# Sheet1.net
KiCad netlist of a schematic drawn in Altium Designer
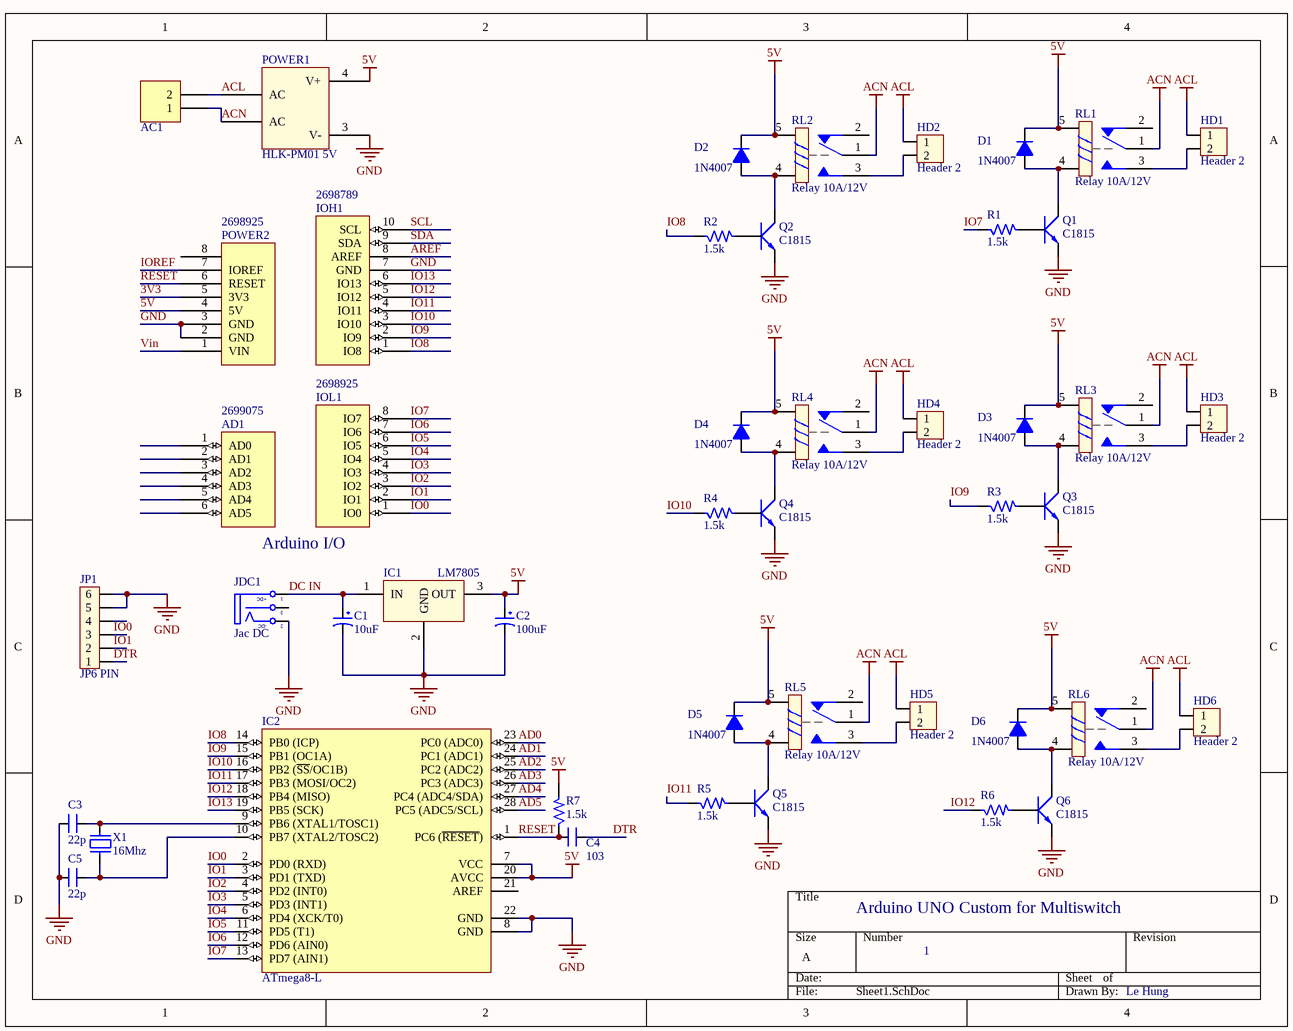
[diagram p0: Sheet1.SchDoc]

(export (version "E")
  (design (tool "Eeschema 10.0.6"))
  (components
    (comp (ref "AC1")
      (value "Header 2_1")
      (footprint "HED2")
      (description "Header, 2-Pin")
      (fields (field (name "MANUFACTURER") "Generic Components"))
      (libsource (lib "syhaunguyen") (part "Header 2_1"))
    )
    (comp (ref "AD1")
      (value "AD")
      (footprint "Header:Header 6x1 8.5mm")
      (fields (field (name "SUPPLIER PART NUMBER 4") "2699075"))
      (libsource (lib "Header") (part "AD"))
    )
    (comp (ref "C1")
      (value "10uF")
      (footprint "CP1/2")
      (description "Cap P  0,1uF < 22uF , 16 - 50V")
      (libsource (lib "syhaunguyen") (part "CP1"))
    )
    (comp (ref "C2")
      (value "100uF")
      (footprint "CP1/2")
      (description "Cap P  0,1uF < 22uF , 16 - 50V")
      (libsource (lib "syhaunguyen") (part "CP1"))
    )
    (comp (ref "C3")
      (value "22p")
      (footprint "CN1.5")
      (description "Cap np 682pF => 104pF")
      (libsource (lib "syhaunguyen") (part "CN1.5"))
    )
    (comp (ref "C4")
      (value "103")
      (footprint "CN1.5")
      (description "Cap np 682pF => 104pF")
      (libsource (lib "syhaunguyen") (part "CN1.5"))
    )
    (comp (ref "C5")
      (value "22p")
      (footprint "CN1.5")
      (description "Cap np 682pF => 104pF")
      (libsource (lib "syhaunguyen") (part "CN1.5"))
    )
    (comp (ref "D1")
      (value "1N4007")
      (footprint "D1A")
      (description "Diode 1A")
      (libsource (lib "syhaunguyen") (part "D1A"))
    )
    (comp (ref "D2")
      (value "1N4007")
      (footprint "D1A")
      (description "Diode 1A")
      (libsource (lib "syhaunguyen") (part "D1A"))
    )
    (comp (ref "D3")
      (value "1N4007")
      (footprint "D1A")
      (description "Diode 1A")
      (libsource (lib "syhaunguyen") (part "D1A"))
    )
    (comp (ref "D4")
      (value "1N4007")
      (footprint "D1A")
      (description "Diode 1A")
      (libsource (lib "syhaunguyen") (part "D1A"))
    )
    (comp (ref "D5")
      (value "1N4007")
      (footprint "D1A")
      (description "Diode 1A")
      (libsource (lib "syhaunguyen") (part "D1A"))
    )
    (comp (ref "D6")
      (value "1N4007")
      (footprint "D1A")
      (description "Diode 1A")
      (libsource (lib "syhaunguyen") (part "D1A"))
    )
    (comp (ref "HD1")
      (value "Header 2")
      (footprint "HED2")
      (description "Header 2 (Green)")
      (libsource (lib "VioletofSun") (part "Hed2"))
    )
    (comp (ref "HD2")
      (value "Header 2")
      (footprint "HED2")
      (description "Header 2 (Green)")
      (libsource (lib "VioletofSun") (part "Hed2"))
    )
    (comp (ref "HD3")
      (value "Header 2")
      (footprint "HED2")
      (description "Header 2 (Green)")
      (libsource (lib "VioletofSun") (part "Hed2"))
    )
    (comp (ref "HD4")
      (value "Header 2")
      (footprint "HED2")
      (description "Header 2 (Green)")
      (libsource (lib "VioletofSun") (part "Hed2"))
    )
    (comp (ref "HD5")
      (value "Header 2")
      (footprint "HED2")
      (description "Header 2 (Green)")
      (libsource (lib "VioletofSun") (part "Hed2"))
    )
    (comp (ref "HD6")
      (value "Header 2")
      (footprint "HED2")
      (description "Header 2 (Green)")
      (libsource (lib "VioletofSun") (part "Hed2"))
    )
    (comp (ref "IC1")
      (value "LM7805")
      (footprint "QTO-220")
      (description "On ap +, from + 5 to + 24VDC")
      (libsource (lib "syhaunguyen") (part "LM78xx"))
    )
    (comp (ref "IC2")
      (value "ATmega8-L")
      (footprint "DIP28/W0.3")
      (description "8-Bit AVR Microcontroller with 8K Bytes of In-System Programmable Flash Memory")
      (libsource (lib "syhaunguyen") (part "ATmega8-L"))
    )
    (comp (ref "IOH1")
      (value "IOH")
      (footprint "Header:Header 10x1 8.5mm")
      (fields (field (name "SUPPLIER PART NUMBER 3") "2698789"))
      (libsource (lib "Header") (part "IOH"))
    )
    (comp (ref "IOL1")
      (value "IOL")
      (footprint "Header 8x1 8.5mm")
      (fields (field (name "SUPPLIER PART NUMBER 4") "2698925"))
      (libsource (lib "Header") (part "IOL"))
    )
    (comp (ref "JDC1")
      (value "Jac DC")
      (footprint "DC-IN")
      (description "Jac DC input")
      (libsource (lib "syhaunguyen") (part "DCIN"))
    )
    (comp (ref "JP1") (value "JP6 PIN") (footprint "JP6") (libsource (lib "syhaunguyen") (part "JP6")))
    (comp (ref "POWER1")
      (value "HLK-PM01 5V")
      (footprint "HK LINK")
      (description "Hi-link HLK-PM01")
      (libsource (lib "Schlib1") (part "Hi link"))
    )
    (comp (ref "POWER2")
      (value "POWER_UNO")
      (footprint "Header 8x1 8.5mm")
      (fields (field (name "SUPPLIER PART NUMBER 4") "2698925"))
      (libsource (lib "Header") (part "POWER_UNO"))
    )
    (comp (ref "Q1")
      (value "C1815")
      (footprint "QTO-92")
      (description "NPN 600mW, ECB")
      (libsource (lib "syhaunguyen") (part "C1815"))
    )
    (comp (ref "Q2")
      (value "C1815")
      (footprint "QTO-92")
      (description "NPN 600mW, ECB")
      (libsource (lib "syhaunguyen") (part "C1815"))
    )
    (comp (ref "Q3")
      (value "C1815")
      (footprint "QTO-92")
      (description "NPN 600mW, ECB")
      (libsource (lib "syhaunguyen") (part "C1815"))
    )
    (comp (ref "Q4")
      (value "C1815")
      (footprint "QTO-92")
      (description "NPN 600mW, ECB")
      (libsource (lib "syhaunguyen") (part "C1815"))
    )
    (comp (ref "Q5")
      (value "C1815")
      (footprint "QTO-92")
      (description "NPN 600mW, ECB")
      (libsource (lib "syhaunguyen") (part "C1815"))
    )
    (comp (ref "Q6")
      (value "C1815")
      (footprint "QTO-92")
      (description "NPN 600mW, ECB")
      (libsource (lib "syhaunguyen") (part "C1815"))
    )
    (comp (ref "R1")
      (value "1.5k")
      (footprint "R1/4W")
      (description "Resistor 1/4W")
      (libsource (lib "syhaunguyen") (part "R"))
    )
    (comp (ref "R2")
      (value "1.5k")
      (footprint "R1/4W")
      (description "Resistor 1/4W")
      (libsource (lib "syhaunguyen") (part "R"))
    )
    (comp (ref "R3")
      (value "1.5k")
      (footprint "R1/4W")
      (description "Resistor 1/4W")
      (libsource (lib "syhaunguyen") (part "R"))
    )
    (comp (ref "R4")
      (value "1.5k")
      (footprint "R1/4W")
      (description "Resistor 1/4W")
      (libsource (lib "syhaunguyen") (part "R"))
    )
    (comp (ref "R5")
      (value "1.5k")
      (footprint "R1/4W")
      (description "Resistor 1/4W")
      (libsource (lib "syhaunguyen") (part "R"))
    )
    (comp (ref "R6")
      (value "1.5k")
      (footprint "R1/4W")
      (description "Resistor 1/4W")
      (libsource (lib "syhaunguyen") (part "R"))
    )
    (comp (ref "R7")
      (value "1.5k")
      (footprint "R1/4W")
      (description "Resistor 1/4W")
      (libsource (lib "syhaunguyen") (part "R"))
    )
    (comp (ref "RL1")
      (value "Relay 10A/12V")
      (footprint "RL_SPDT_10A")
      (description "Relay SPDT,10A - 12VDC 5 Pin")
      (libsource (lib "syhaunguyen") (part "Relay 1"))
    )
    (comp (ref "RL2")
      (value "Relay 10A/12V")
      (footprint "RL_SPDT_10A")
      (description "Relay SPDT,10A - 12VDC 5 Pin")
      (libsource (lib "syhaunguyen") (part "Relay 1"))
    )
    (comp (ref "RL3")
      (value "Relay 10A/12V")
      (footprint "RL_SPDT_10A")
      (description "Relay SPDT,10A - 12VDC 5 Pin")
      (libsource (lib "syhaunguyen") (part "Relay 1"))
    )
    (comp (ref "RL4")
      (value "Relay 10A/12V")
      (footprint "RL_SPDT_10A")
      (description "Relay SPDT,10A - 12VDC 5 Pin")
      (libsource (lib "syhaunguyen") (part "Relay 1"))
    )
    (comp (ref "RL5")
      (value "Relay 10A/12V")
      (footprint "RL_SPDT_10A")
      (description "Relay SPDT,10A - 12VDC 5 Pin")
      (libsource (lib "syhaunguyen") (part "Relay 1"))
    )
    (comp (ref "RL6")
      (value "Relay 10A/12V")
      (footprint "RL_SPDT_10A")
      (description "Relay SPDT,10A - 12VDC 5 Pin")
      (libsource (lib "syhaunguyen") (part "Relay 1"))
    )
    (comp (ref "X1")
      (value "16Mhz")
      (footprint "XT2")
      (description "Crystal For all Crystal 2pin.")
      (libsource (lib "syhaunguyen") (part "XT2"))
    )
  )
  (nets
    (net (code "1") (name "/3V3") (class "Default")
      (node (ref "POWER2") (pin "5") (pinfunction "3V3_5") (pintype "power_in"))
    )
    (net (code "3") (name "/AD0") (class "Default")
      (node (ref "IC2") (pin "23") (pinfunction "PC0_(ADC0)_23") (pintype "bidirectional"))
    )
    (net (code "4") (name "/AD1") (class "Default")
      (node (ref "IC2") (pin "24") (pinfunction "PC1_(ADC1)_24") (pintype "bidirectional"))
    )
    (net (code "5") (name "/AD2") (class "Default")
      (node (ref "IC2") (pin "25") (pinfunction "PC2_(ADC2)_25") (pintype "bidirectional"))
    )
    (net (code "6") (name "/AD3") (class "Default")
      (node (ref "IC2") (pin "26") (pinfunction "PC3_(ADC3)_26") (pintype "bidirectional"))
    )
    (net (code "7") (name "/AD4") (class "Default")
      (node (ref "IC2") (pin "27") (pinfunction "PC4_(ADC4/SDA)_27") (pintype "bidirectional"))
    )
    (net (code "8") (name "/AD5") (class "Default")
      (node (ref "IC2") (pin "28") (pinfunction "PC5_(ADC5/SCL)_28") (pintype "bidirectional"))
    )
    (net (code "9") (name "/AREF") (class "Default")
      (node (ref "IOH1") (pin "8") (pinfunction "AREF_8") (pintype "passive"))
    )
    (net (code "10") (name "/DC IN") (class "Default")
      (node (ref "C1") (pin "1") (pinfunction "1_1") (pintype "passive"))
      (node (ref "IC1") (pin "1") (pinfunction "IN_1") (pintype "passive"))
      (node (ref "JDC1") (pin "1") (pinfunction "T_1") (pintype "passive"))
    )
    (net (code "11") (name "/DTR") (class "Default")
      (node (ref "C4") (pin "2") (pinfunction "2_2") (pintype "passive"))
      (node (ref "JP1") (pin "1") (pinfunction "1_1") (pintype "passive"))
    )
    (net (code "12") (name "/IO0") (class "Default")
      (node (ref "IC2") (pin "2") (pinfunction "PD0_(RXD)_2") (pintype "bidirectional"))
      (node (ref "IOL1") (pin "1") (pinfunction "IO0_1") (pintype "bidirectional"))
      (node (ref "JP1") (pin "3") (pinfunction "3_3") (pintype "passive"))
    )
    (net (code "13") (name "/IO1") (class "Default")
      (node (ref "IC2") (pin "3") (pinfunction "PD1_(TXD)_3") (pintype "bidirectional"))
      (node (ref "IOL1") (pin "2") (pinfunction "IO1_2") (pintype "bidirectional"))
      (node (ref "JP1") (pin "2") (pinfunction "2_2") (pintype "passive"))
    )
    (net (code "14") (name "/IO2") (class "Default")
      (node (ref "IC2") (pin "4") (pinfunction "PD2_(INT0)_4") (pintype "bidirectional"))
      (node (ref "IOL1") (pin "3") (pinfunction "IO2_3") (pintype "bidirectional"))
    )
    (net (code "15") (name "/IO3") (class "Default")
      (node (ref "IC2") (pin "5") (pinfunction "PD3_(INT1)_5") (pintype "bidirectional"))
      (node (ref "IOL1") (pin "4") (pinfunction "IO3_4") (pintype "bidirectional"))
    )
    (net (code "16") (name "/IO4") (class "Default")
      (node (ref "IC2") (pin "6") (pinfunction "PD4_(XCK/T0)_6") (pintype "bidirectional"))
      (node (ref "IOL1") (pin "5") (pinfunction "IO4_5") (pintype "bidirectional"))
    )
    (net (code "17") (name "/IO5") (class "Default")
      (node (ref "IC2") (pin "11") (pinfunction "PD5_(T1)_11") (pintype "bidirectional"))
      (node (ref "IOL1") (pin "6") (pinfunction "IO5_6") (pintype "bidirectional"))
    )
    (net (code "18") (name "/IO6") (class "Default")
      (node (ref "IC2") (pin "12") (pinfunction "PD6_(AIN0)_12") (pintype "bidirectional"))
      (node (ref "IOL1") (pin "7") (pinfunction "IO6_7") (pintype "bidirectional"))
    )
    (net (code "19") (name "/IO7") (class "Default")
      (node (ref "IC2") (pin "13") (pinfunction "PD7_(AIN1)_13") (pintype "bidirectional"))
      (node (ref "IOL1") (pin "8") (pinfunction "IO7_8") (pintype "bidirectional"))
      (node (ref "R1") (pin "1") (pinfunction "1_1") (pintype "passive"))
    )
    (net (code "20") (name "/IO8") (class "Default")
      (node (ref "IC2") (pin "14") (pinfunction "PB0_(ICP)_14") (pintype "bidirectional"))
      (node (ref "IOH1") (pin "1") (pinfunction "IO8_1") (pintype "bidirectional"))
      (node (ref "R2") (pin "1") (pinfunction "1_1") (pintype "passive"))
    )
    (net (code "21") (name "/IO9") (class "Default")
      (node (ref "IC2") (pin "15") (pinfunction "PB1_(OC1A)_15") (pintype "bidirectional"))
      (node (ref "IOH1") (pin "2") (pinfunction "IO9_2") (pintype "bidirectional"))
      (node (ref "R3") (pin "1") (pinfunction "1_1") (pintype "passive"))
    )
    (net (code "22") (name "/IO10") (class "Default")
      (node (ref "IC2") (pin "16") (pinfunction "PB2_(~{SS}/OC1B)_16") (pintype "bidirectional"))
      (node (ref "IOH1") (pin "3") (pinfunction "IO10_3") (pintype "bidirectional"))
      (node (ref "R4") (pin "1") (pinfunction "1_1") (pintype "passive"))
    )
    (net (code "23") (name "/IO11") (class "Default")
      (node (ref "IC2") (pin "17") (pinfunction "PB3_(MOSI/OC2)_17") (pintype "bidirectional"))
      (node (ref "IOH1") (pin "4") (pinfunction "IO11_4") (pintype "bidirectional"))
      (node (ref "R5") (pin "1") (pinfunction "1_1") (pintype "passive"))
    )
    (net (code "24") (name "/IO12") (class "Default")
      (node (ref "IC2") (pin "18") (pinfunction "PB4_(MISO)_18") (pintype "bidirectional"))
      (node (ref "IOH1") (pin "5") (pinfunction "IO12_5") (pintype "bidirectional"))
      (node (ref "R6") (pin "1") (pinfunction "1_1") (pintype "passive"))
    )
    (net (code "25") (name "/IO13") (class "Default")
      (node (ref "IC2") (pin "19") (pinfunction "PB5_(SCK)_19") (pintype "bidirectional"))
      (node (ref "IOH1") (pin "6") (pinfunction "IO13_6") (pintype "bidirectional"))
    )
    (net (code "26") (name "/IOREF") (class "Default")
      (node (ref "POWER2") (pin "7") (pinfunction "IOREF_7") (pintype "power_in"))
    )
    (net (code "27") (name "/RESET") (class "Default")
      (node (ref "C4") (pin "1") (pinfunction "1_1") (pintype "passive"))
      (node (ref "IC2") (pin "1") (pinfunction "PC6_(~{RESET})_1") (pintype "bidirectional"))
      (node (ref "POWER2") (pin "6") (pinfunction "RESET_6") (pintype "passive"))
      (node (ref "R7") (pin "1") (pinfunction "1_1") (pintype "passive"))
    )
    (net (code "28") (name "/SCL") (class "Default")
      (node (ref "IOH1") (pin "10") (pinfunction "SCL_10") (pintype "bidirectional"))
    )
    (net (code "29") (name "/SDA") (class "Default")
      (node (ref "IOH1") (pin "9") (pinfunction "SDA_9") (pintype "bidirectional"))
    )
    (net (code "30") (name "/Vin") (class "Default")
      (node (ref "POWER2") (pin "1") (pinfunction "VIN_1") (pintype "power_in"))
    )
    (net (code "31") (name "5V") (class "Default")
      (node (ref "C2") (pin "1") (pinfunction "1_1") (pintype "passive"))
      (node (ref "D1") (pin "2") (pinfunction "K_2") (pintype "passive"))
      (node (ref "D2") (pin "2") (pinfunction "K_2") (pintype "passive"))
      (node (ref "D3") (pin "2") (pinfunction "K_2") (pintype "passive"))
      (node (ref "D4") (pin "2") (pinfunction "K_2") (pintype "passive"))
      (node (ref "D5") (pin "2") (pinfunction "K_2") (pintype "passive"))
      (node (ref "D6") (pin "2") (pinfunction "K_2") (pintype "passive"))
      (node (ref "IC1") (pin "3") (pinfunction "OUT_3") (pintype "passive"))
      (node (ref "IC2") (pin "20") (pinfunction "AVCC_20") (pintype "power_in"))
      (node (ref "IC2") (pin "7") (pinfunction "VCC_7") (pintype "power_in"))
      (node (ref "POWER1") (pin "4") (pinfunction "V+_4") (pintype "passive"))
      (node (ref "POWER2") (pin "4") (pinfunction "5V_4") (pintype "power_in"))
      (node (ref "R7") (pin "2") (pinfunction "2_2") (pintype "passive"))
      (node (ref "RL1") (pin "5") (pinfunction "5_5") (pintype "passive"))
      (node (ref "RL2") (pin "5") (pinfunction "5_5") (pintype "passive"))
      (node (ref "RL3") (pin "5") (pinfunction "5_5") (pintype "passive"))
      (node (ref "RL4") (pin "5") (pinfunction "5_5") (pintype "passive"))
      (node (ref "RL5") (pin "5") (pinfunction "5_5") (pintype "passive"))
      (node (ref "RL6") (pin "5") (pinfunction "5_5") (pintype "passive"))
    )
    (net (code "32") (name "ACL") (class "Default")
      (node (ref "AC1") (pin "2") (pinfunction "2_2") (pintype "passive"))
      (node (ref "HD1") (pin "1") (pinfunction "1_1") (pintype "passive"))
      (node (ref "HD2") (pin "1") (pinfunction "1_1") (pintype "passive"))
      (node (ref "HD3") (pin "1") (pinfunction "1_1") (pintype "passive"))
      (node (ref "HD4") (pin "1") (pinfunction "1_1") (pintype "passive"))
      (node (ref "HD5") (pin "1") (pinfunction "1_1") (pintype "passive"))
      (node (ref "HD6") (pin "1") (pinfunction "1_1") (pintype "passive"))
      (node (ref "POWER1") (pin "2") (pinfunction "AC_2") (pintype "passive"))
    )
    (net (code "33") (name "ACN") (class "Default")
      (node (ref "AC1") (pin "1") (pinfunction "1_1") (pintype "passive"))
      (node (ref "POWER1") (pin "1") (pinfunction "AC_1") (pintype "passive"))
      (node (ref "RL1") (pin "1") (pinfunction "1_1") (pintype "passive"))
      (node (ref "RL2") (pin "1") (pinfunction "1_1") (pintype "passive"))
      (node (ref "RL3") (pin "1") (pinfunction "1_1") (pintype "passive"))
      (node (ref "RL4") (pin "1") (pinfunction "1_1") (pintype "passive"))
      (node (ref "RL5") (pin "1") (pinfunction "1_1") (pintype "passive"))
      (node (ref "RL6") (pin "1") (pinfunction "1_1") (pintype "passive"))
    )
    (net (code "34") (name "GND") (class "Default")
      (node (ref "C1") (pin "2") (pinfunction "2_2") (pintype "passive"))
      (node (ref "C2") (pin "2") (pinfunction "2_2") (pintype "passive"))
      (node (ref "C3") (pin "1") (pinfunction "1_1") (pintype "passive"))
      (node (ref "C5") (pin "1") (pinfunction "1_1") (pintype "passive"))
      (node (ref "IC1") (pin "2") (pinfunction "GND_2") (pintype "passive"))
      (node (ref "IC2") (pin "22") (pinfunction "GND_22") (pintype "power_in"))
      (node (ref "IC2") (pin "8") (pinfunction "GND_8") (pintype "power_in"))
      (node (ref "IOH1") (pin "7") (pinfunction "GND_7") (pintype "power_in"))
      (node (ref "JDC1") (pin "2") (pinfunction "TN_2") (pintype "passive"))
      (node (ref "JP1") (pin "5") (pinfunction "5_5") (pintype "passive"))
      (node (ref "JP1") (pin "6") (pinfunction "6_6") (pintype "passive"))
      (node (ref "POWER1") (pin "3") (pinfunction "V-_3") (pintype "passive"))
      (node (ref "POWER2") (pin "2") (pinfunction "GND_2") (pintype "power_in"))
      (node (ref "POWER2") (pin "3") (pinfunction "GND_3") (pintype "power_in"))
      (node (ref "Q1") (pin "1") (pinfunction "E_1") (pintype "passive"))
      (node (ref "Q2") (pin "1") (pinfunction "E_1") (pintype "passive"))
      (node (ref "Q3") (pin "1") (pinfunction "E_1") (pintype "passive"))
      (node (ref "Q4") (pin "1") (pinfunction "E_1") (pintype "passive"))
      (node (ref "Q5") (pin "1") (pinfunction "E_1") (pintype "passive"))
      (node (ref "Q6") (pin "1") (pinfunction "E_1") (pintype "passive"))
    )
    (net (code "35") (name "Net-(D1-A)") (class "Default")
      (node (ref "D1") (pin "1") (pinfunction "A_1") (pintype "passive"))
      (node (ref "Q1") (pin "2") (pinfunction "C_2") (pintype "passive"))
      (node (ref "RL1") (pin "4") (pinfunction "4_4") (pintype "passive"))
    )
    (net (code "36") (name "Net-(D2-A)") (class "Default")
      (node (ref "D2") (pin "1") (pinfunction "A_1") (pintype "passive"))
      (node (ref "Q2") (pin "2") (pinfunction "C_2") (pintype "passive"))
      (node (ref "RL2") (pin "4") (pinfunction "4_4") (pintype "passive"))
    )
    (net (code "37") (name "Net-(D3-A)") (class "Default")
      (node (ref "D3") (pin "1") (pinfunction "A_1") (pintype "passive"))
      (node (ref "Q3") (pin "2") (pinfunction "C_2") (pintype "passive"))
      (node (ref "RL3") (pin "4") (pinfunction "4_4") (pintype "passive"))
    )
    (net (code "38") (name "Net-(D4-A)") (class "Default")
      (node (ref "D4") (pin "1") (pinfunction "A_1") (pintype "passive"))
      (node (ref "Q4") (pin "2") (pinfunction "C_2") (pintype "passive"))
      (node (ref "RL4") (pin "4") (pinfunction "4_4") (pintype "passive"))
    )
    (net (code "39") (name "Net-(D5-A)") (class "Default")
      (node (ref "D5") (pin "1") (pinfunction "A_1") (pintype "passive"))
      (node (ref "Q5") (pin "2") (pinfunction "C_2") (pintype "passive"))
      (node (ref "RL5") (pin "4") (pinfunction "4_4") (pintype "passive"))
    )
    (net (code "40") (name "Net-(D6-A)") (class "Default")
      (node (ref "D6") (pin "1") (pinfunction "A_1") (pintype "passive"))
      (node (ref "Q6") (pin "2") (pinfunction "C_2") (pintype "passive"))
      (node (ref "RL6") (pin "4") (pinfunction "4_4") (pintype "passive"))
    )
    (net (code "41") (name "Net-(HD1-Pad2)") (class "Default")
      (node (ref "HD1") (pin "2") (pinfunction "2_2") (pintype "passive"))
      (node (ref "RL1") (pin "3") (pinfunction "3_3") (pintype "passive"))
    )
    (net (code "42") (name "Net-(HD2-Pad2)") (class "Default")
      (node (ref "HD2") (pin "2") (pinfunction "2_2") (pintype "passive"))
      (node (ref "RL2") (pin "3") (pinfunction "3_3") (pintype "passive"))
    )
    (net (code "43") (name "Net-(HD3-Pad2)") (class "Default")
      (node (ref "HD3") (pin "2") (pinfunction "2_2") (pintype "passive"))
      (node (ref "RL3") (pin "3") (pinfunction "3_3") (pintype "passive"))
    )
    (net (code "44") (name "Net-(HD4-Pad2)") (class "Default")
      (node (ref "HD4") (pin "2") (pinfunction "2_2") (pintype "passive"))
      (node (ref "RL4") (pin "3") (pinfunction "3_3") (pintype "passive"))
    )
    (net (code "45") (name "Net-(HD5-Pad2)") (class "Default")
      (node (ref "HD5") (pin "2") (pinfunction "2_2") (pintype "passive"))
      (node (ref "RL5") (pin "3") (pinfunction "3_3") (pintype "passive"))
    )
    (net (code "46") (name "Net-(HD6-Pad2)") (class "Default")
      (node (ref "HD6") (pin "2") (pinfunction "2_2") (pintype "passive"))
      (node (ref "RL6") (pin "3") (pinfunction "3_3") (pintype "passive"))
    )
    (net (code "47") (name "Net-(IC2-PB6_(XTAL1{slash}TOSC1))") (class "Default")
      (node (ref "C3") (pin "2") (pinfunction "2_2") (pintype "passive"))
      (node (ref "IC2") (pin "9") (pinfunction "PB6_(XTAL1/TOSC1)_9") (pintype "bidirectional"))
      (node (ref "X1") (pin "2") (pinfunction "2_2") (pintype "passive"))
    )
    (net (code "48") (name "Net-(IC2-PB7_(XTAL2{slash}TOSC2))") (class "Default")
      (node (ref "C5") (pin "2") (pinfunction "2_2") (pintype "passive"))
      (node (ref "IC2") (pin "10") (pinfunction "PB7_(XTAL2/TOSC2)_10") (pintype "bidirectional"))
      (node (ref "X1") (pin "1") (pinfunction "1_1") (pintype "passive"))
    )
    (net (code "49") (name "Net-(Q1-B)") (class "Default")
      (node (ref "Q1") (pin "3") (pinfunction "B_3") (pintype "passive"))
      (node (ref "R1") (pin "2") (pinfunction "2_2") (pintype "passive"))
    )
    (net (code "50") (name "Net-(Q2-B)") (class "Default")
      (node (ref "Q2") (pin "3") (pinfunction "B_3") (pintype "passive"))
      (node (ref "R2") (pin "2") (pinfunction "2_2") (pintype "passive"))
    )
    (net (code "51") (name "Net-(Q3-B)") (class "Default")
      (node (ref "Q3") (pin "3") (pinfunction "B_3") (pintype "passive"))
      (node (ref "R3") (pin "2") (pinfunction "2_2") (pintype "passive"))
    )
    (net (code "52") (name "Net-(Q4-B)") (class "Default")
      (node (ref "Q4") (pin "3") (pinfunction "B_3") (pintype "passive"))
      (node (ref "R4") (pin "2") (pinfunction "2_2") (pintype "passive"))
    )
    (net (code "53") (name "Net-(Q5-B)") (class "Default")
      (node (ref "Q5") (pin "3") (pinfunction "B_3") (pintype "passive"))
      (node (ref "R5") (pin "2") (pinfunction "2_2") (pintype "passive"))
    )
    (net (code "54") (name "Net-(Q6-B)") (class "Default")
      (node (ref "Q6") (pin "3") (pinfunction "B_3") (pintype "passive"))
      (node (ref "R6") (pin "2") (pinfunction "2_2") (pintype "passive"))
    )
    (net (code "55") (name "unconnected-(AD1-AD0-Pad1)") (class "Default")
      (node (ref "AD1") (pin "1") (pinfunction "AD0_1") (pintype "bidirectional"))
    )
    (net (code "56") (name "unconnected-(AD1-AD1-Pad2)") (class "Default")
      (node (ref "AD1") (pin "2") (pinfunction "AD1_2") (pintype "bidirectional"))
    )
    (net (code "57") (name "unconnected-(AD1-AD2-Pad3)") (class "Default")
      (node (ref "AD1") (pin "3") (pinfunction "AD2_3") (pintype "bidirectional"))
    )
    (net (code "58") (name "unconnected-(AD1-AD3-Pad4)") (class "Default")
      (node (ref "AD1") (pin "4") (pinfunction "AD3_4") (pintype "bidirectional"))
    )
    (net (code "59") (name "unconnected-(AD1-AD4-Pad5)") (class "Default")
      (node (ref "AD1") (pin "5") (pinfunction "AD4_5") (pintype "bidirectional"))
    )
    (net (code "60") (name "unconnected-(AD1-AD5-Pad6)") (class "Default")
      (node (ref "AD1") (pin "6") (pinfunction "AD5_6") (pintype "bidirectional"))
    )
    (net (code "61") (name "unconnected-(IC2-AREF-Pad21)") (class "Default")
      (node (ref "IC2") (pin "21") (pinfunction "AREF_21") (pintype "passive"))
    )
    (net (code "62") (name "unconnected-(JDC1-S-Pad3)") (class "Default")
      (node (ref "JDC1") (pin "3") (pinfunction "S_3") (pintype "power_in"))
    )
    (net (code "63") (name "unconnected-(JP1-Pad4)") (class "Default")
      (node (ref "JP1") (pin "4") (pinfunction "4_4") (pintype "passive"))
    )
    (net (code "64") (name "unconnected-(POWER2-Pad8)") (class "Default")
      (node (ref "POWER2") (pin "8") (pintype "passive"))
    )
    (net (code "65") (name "unconnected-(RL1-Pad2)") (class "Default")
      (node (ref "RL1") (pin "2") (pinfunction "2_2") (pintype "passive"))
    )
    (net (code "66") (name "unconnected-(RL2-Pad2)") (class "Default")
      (node (ref "RL2") (pin "2") (pinfunction "2_2") (pintype "passive"))
    )
    (net (code "67") (name "unconnected-(RL3-Pad2)") (class "Default")
      (node (ref "RL3") (pin "2") (pinfunction "2_2") (pintype "passive"))
    )
    (net (code "68") (name "unconnected-(RL4-Pad2)") (class "Default")
      (node (ref "RL4") (pin "2") (pinfunction "2_2") (pintype "passive"))
    )
    (net (code "69") (name "unconnected-(RL5-Pad2)") (class "Default")
      (node (ref "RL5") (pin "2") (pinfunction "2_2") (pintype "passive"))
    )
    (net (code "70") (name "unconnected-(RL6-Pad2)") (class "Default")
      (node (ref "RL6") (pin "2") (pinfunction "2_2") (pintype "passive"))
    )
  )
)
